# High_Side_Switch.net
KiCad netlist of a schematic drawn in Altium Designer
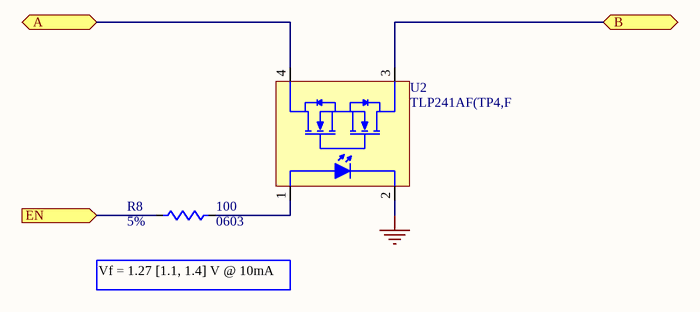
[diagram p0: High_Side_Switch.SchDoc]

(export (version "E")
  (design (tool "Eeschema 10.0.6"))
  (components
    (comp (ref "R8")
      (value "100")
      (footprint "RESC1508X09N")
      (description "RES 100 OHM 5% 0603")
      (fields (field (name "TOLERANCE") "5%") (field (name "PACKAGE") "0603") (field (name "Comment") "RES"))
      (libsource (lib "resistors") (part "RES"))
    )
    (comp (ref "U2")
      (value "SSR_SPST-NO")
      (footprint "SOP254P1000X425-4N_TLP241AF")
      (description "SSR RELAY SPST-NO 2A 0-40V")
      (fields (field (name "MANUFACTURER PART NUMBER 1") "TLP241AF(TP4,F"))
      (libsource (lib "discretes") (part "SSR_SPST-NO"))
    )
  )
  (nets
    (net (code "1") (name "/A") (class "Default")
      (node (ref "U2") (pin "4") (pinfunction "4_4") (pintype "passive"))
    )
    (net (code "2") (name "/B") (class "Default")
      (node (ref "U2") (pin "3") (pinfunction "3_3") (pintype "passive"))
    )
    (net (code "3") (name "/EN") (class "Default")
      (node (ref "R8") (pin "1") (pinfunction "1_1") (pintype "passive"))
    )
    (net (code "4") (name "GND") (class "Default")
      (node (ref "U2") (pin "2") (pinfunction "2_2") (pintype "passive"))
    )
    (net (code "5") (name "Net-(R8-Pad2)") (class "Default")
      (node (ref "R8") (pin "2") (pinfunction "2_2") (pintype "passive"))
      (node (ref "U2") (pin "1") (pinfunction "1_1") (pintype "passive"))
    )
  )
)
